# AHE.net
KiCad netlist of a schematic drawn in EAGLE
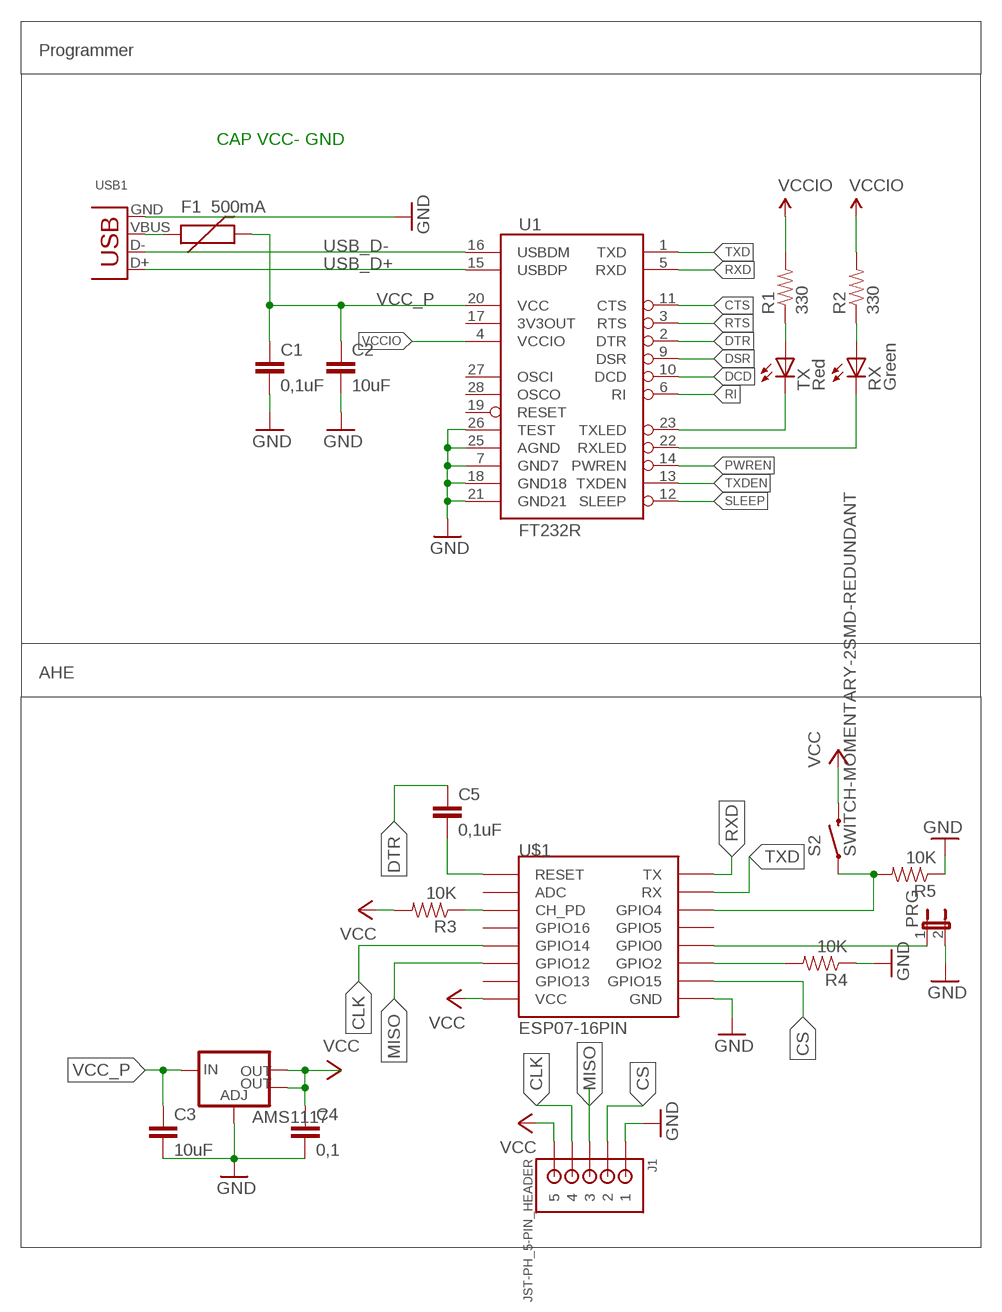
[diagram p0: schematic, sheet 1]

(export (version "E")
  (design (tool "Eeschema 10.0.6"))
  (components
    (comp (ref "AMS1117")
      (value "V_REG_LM1117SOT223")
      (footprint "eagle-import:SOT223")
      (libsource (lib "eagle-import") (part "V_REG_LM1117SOT223"))
    )
    (comp (ref "C1")
      (value "0,1uF")
      (footprint "eagle-import:0805-CAP")
      (libsource (lib "eagle-import") (part "10UF10V10%(0805)"))
    )
    (comp (ref "C2")
      (value "10uF")
      (footprint "eagle-import:0805-CAP")
      (libsource (lib "eagle-import") (part "10UF10V10%(0805)"))
    )
    (comp (ref "C3")
      (value "10uF")
      (footprint "eagle-import:0805-CAP")
      (libsource (lib "eagle-import") (part "10UF10V10%(0805)"))
    )
    (comp (ref "C4")
      (value "0,1")
      (footprint "eagle-import:0805-CAP")
      (libsource (lib "eagle-import") (part "10UF10V10%(0805)"))
    )
    (comp (ref "C5")
      (value "0,1uF")
      (footprint "eagle-import:0805-CAP")
      (libsource (lib "eagle-import") (part "10UF10V10%(0805)"))
    )
    (comp (ref "F1")
      (value "500mA")
      (footprint "eagle-import:PTC-1206")
      (libsource (lib "eagle-import") (part "PTCSMD"))
    )
    (comp (ref "J1")
      (value "JST-PH_5-PIN_HEADER")
      (footprint "eagle-import:JST_B5B-PH_HEADER")
      (libsource (lib "eagle-import") (part "JST-PH_5-PIN_HEADER"))
    )
    (comp (ref "PRG")
      (value "JP1E")
      (footprint "eagle-import:JP1")
      (libsource (lib "eagle-import") (part "JP1E"))
    )
    (comp (ref "R1")
      (value "330")
      (footprint "eagle-import:0805")
      (libsource (lib "eagle-import") (part "0.22OHM-1/4W-1%(0805)"))
    )
    (comp (ref "R2")
      (value "330")
      (footprint "eagle-import:0805")
      (libsource (lib "eagle-import") (part "0.22OHM-1/4W-1%(0805)"))
    )
    (comp (ref "R3")
      (value "10K")
      (footprint "eagle-import:0805")
      (libsource (lib "eagle-import") (part "0.22OHM-1/4W-1%(0805)"))
    )
    (comp (ref "R4")
      (value "10K")
      (footprint "eagle-import:0805")
      (libsource (lib "eagle-import") (part "0.22OHM-1/4W-1%(0805)"))
    )
    (comp (ref "R5")
      (value "10K")
      (footprint "eagle-import:0805")
      (libsource (lib "eagle-import") (part "0.22OHM-1/4W-1%(0805)"))
    )
    (comp (ref "RX")
      (value "Green")
      (footprint "eagle-import:SML0805")
      (libsource (lib "eagle-import") (part "LEDSML0805"))
    )
    (comp (ref "S2")
      (value "SWITCH-MOMENTARY-2SMD-REDUNDANT")
      (footprint "eagle-import:TACTILE-SWITCH-SMD")
      (libsource (lib "eagle-import") (part "SWITCH-MOMENTARY-2SMD-REDUNDANT"))
    )
    (comp (ref "TX")
      (value "Red")
      (footprint "eagle-import:SML0805")
      (libsource (lib "eagle-import") (part "LEDSML0805"))
    )
    (comp (ref "U$1")
      (value "ESP07-16PIN")
      (footprint "eagle-import:ESP07-16PIN")
      (libsource (lib "eagle-import") (part "ESP07-16PIN"))
    )
    (comp (ref "U1")
      (value "FT232R")
      (footprint "eagle-import:SSOP28DB")
      (libsource (lib "eagle-import") (part "FT232RLSSOP"))
    )
    (comp (ref "USB1")
      (value "USB-MB-S")
      (footprint "eagle-import:USB-MB-S")
      (libsource (lib "eagle-import") (part "USB-MB-S"))
    )
  )
  (nets
    (net (code "1") (name "/USB_D+") (class "Default")
      (node (ref "U1") (pin "15") (pinfunction "USBDP_15") (pintype "bidirectional"))
      (node (ref "USB1") (pin "D+") (pinfunction "D+_D+") (pintype "bidirectional"))
    )
    (net (code "2") (name "/USB_D-") (class "Default")
      (node (ref "U1") (pin "16") (pinfunction "USBDM_16") (pintype "bidirectional"))
      (node (ref "USB1") (pin "D-") (pinfunction "D-_D-") (pintype "bidirectional"))
    )
    (net (code "3") (name "CLK") (class "Default")
      (node (ref "J1") (pin "P4") (pinfunction "4_P4") (pintype "bidirectional"))
      (node (ref "U$1") (pin "GPIO14") (pinfunction "GPIO14_GPIO14") (pintype "bidirectional"))
    )
    (net (code "4") (name "CS") (class "Default")
      (node (ref "J1") (pin "P2") (pinfunction "2_P2") (pintype "bidirectional"))
      (node (ref "U$1") (pin "GPIO15") (pinfunction "GPIO15_GPIO15") (pintype "bidirectional"))
    )
    (net (code "5") (name "CTS") (class "Default")
      (node (ref "U1") (pin "11") (pinfunction "CTS_11") (pintype "input"))
    )
    (net (code "6") (name "DCD") (class "Default")
      (node (ref "U1") (pin "10") (pinfunction "DCD_10") (pintype "input"))
    )
    (net (code "7") (name "DSR") (class "Default")
      (node (ref "U1") (pin "9") (pinfunction "DSR_9") (pintype "input"))
    )
    (net (code "8") (name "DTR") (class "Default")
      (node (ref "C5") (pin "1") (pinfunction "1_1") (pintype "passive"))
      (node (ref "U1") (pin "2") (pinfunction "DTR_2") (pintype "output"))
    )
    (net (code "9") (name "GND") (class "Default")
      (node (ref "AMS1117") (pin "1") (pinfunction "ADJ_1") (pintype "input"))
      (node (ref "C1") (pin "2") (pinfunction "2_2") (pintype "passive"))
      (node (ref "C2") (pin "2") (pinfunction "2_2") (pintype "passive"))
      (node (ref "C3") (pin "2") (pinfunction "2_2") (pintype "passive"))
      (node (ref "C4") (pin "2") (pinfunction "2_2") (pintype "passive"))
      (node (ref "J1") (pin "P1") (pinfunction "1_P1") (pintype "bidirectional"))
      (node (ref "PRG") (pin "2") (pinfunction "2_2") (pintype "passive"))
      (node (ref "R4") (pin "1") (pinfunction "1_1") (pintype "passive"))
      (node (ref "R5") (pin "1") (pinfunction "1_1") (pintype "passive"))
      (node (ref "U$1") (pin "GND") (pinfunction "GND_GND") (pintype "bidirectional"))
      (node (ref "U1") (pin "18") (pinfunction "GND18_18") (pintype "power_in"))
      (node (ref "U1") (pin "21") (pinfunction "GND21_21") (pintype "power_in"))
      (node (ref "U1") (pin "25") (pinfunction "AGND_25") (pintype "power_in"))
      (node (ref "U1") (pin "26") (pinfunction "TEST_26") (pintype "input"))
      (node (ref "U1") (pin "7") (pinfunction "GND7_7") (pintype "power_in"))
      (node (ref "USB1") (pin "GND") (pinfunction "GND_GND") (pintype "bidirectional"))
    )
    (net (code "10") (name "MISO") (class "Default")
      (node (ref "J1") (pin "P3") (pinfunction "3_P3") (pintype "bidirectional"))
      (node (ref "U$1") (pin "GPIO12") (pinfunction "GPIO12_GPIO12") (pintype "bidirectional"))
    )
    (net (code "11") (name "Net-(F1-Pad1)") (class "Default")
      (node (ref "F1") (pin "1") (pinfunction "1_1") (pintype "bidirectional"))
      (node (ref "USB1") (pin "VBUS") (pinfunction "VBUS_VBUS") (pintype "bidirectional"))
    )
    (net (code "12") (name "Net-(PRG-Pad1)") (class "Default")
      (node (ref "PRG") (pin "1") (pinfunction "1_1") (pintype "passive"))
      (node (ref "U$1") (pin "GPIO0") (pinfunction "GPIO0_GPIO0") (pintype "bidirectional"))
    )
    (net (code "13") (name "Net-(R1-Pad1)") (class "Default")
      (node (ref "R1") (pin "1") (pinfunction "1_1") (pintype "passive"))
      (node (ref "TX") (pin "A") (pinfunction "A_A") (pintype "passive"))
    )
    (net (code "14") (name "Net-(R2-Pad1)") (class "Default")
      (node (ref "R2") (pin "1") (pinfunction "1_1") (pintype "passive"))
      (node (ref "RX") (pin "A") (pinfunction "A_A") (pintype "passive"))
    )
    (net (code "15") (name "Net-(R3-Pad1)") (class "Default")
      (node (ref "R3") (pin "1") (pinfunction "1_1") (pintype "passive"))
      (node (ref "U$1") (pin "CH_PD") (pinfunction "CH_PD_CH_PD") (pintype "bidirectional"))
    )
    (net (code "16") (name "Net-(R4-Pad2)") (class "Default")
      (node (ref "R4") (pin "2") (pinfunction "2_2") (pintype "passive"))
      (node (ref "U$1") (pin "GPIO2") (pinfunction "GPIO2_GPIO2") (pintype "bidirectional"))
    )
    (net (code "17") (name "Net-(R5-Pad2)") (class "Default")
      (node (ref "R5") (pin "2") (pinfunction "2_2") (pintype "passive"))
      (node (ref "S2") (pin "1") (pinfunction "1_1") (pintype "passive"))
      (node (ref "S2") (pin "2") (pinfunction "1_2") (pintype "passive"))
      (node (ref "U$1") (pin "GPIO4") (pinfunction "GPIO4_GPIO4") (pintype "bidirectional"))
    )
    (net (code "18") (name "Net-(U$1-RESET)") (class "Default")
      (node (ref "C5") (pin "2") (pinfunction "2_2") (pintype "passive"))
      (node (ref "U$1") (pin "REST") (pinfunction "RESET_REST") (pintype "bidirectional"))
    )
    (net (code "19") (name "Net-(U1-RXLED)") (class "Default")
      (node (ref "RX") (pin "C") (pinfunction "C_C") (pintype "passive"))
      (node (ref "U1") (pin "22") (pinfunction "RXLED_22") (pintype "input"))
    )
    (net (code "20") (name "Net-(U1-TXLED)") (class "Default")
      (node (ref "TX") (pin "C") (pinfunction "C_C") (pintype "passive"))
      (node (ref "U1") (pin "23") (pinfunction "TXLED_23") (pintype "input"))
    )
    (net (code "21") (name "PWREN") (class "Default")
      (node (ref "U1") (pin "14") (pinfunction "PWREN_14") (pintype "input"))
    )
    (net (code "22") (name "RI") (class "Default")
      (node (ref "U1") (pin "6") (pinfunction "RI_6") (pintype "input"))
    )
    (net (code "23") (name "RTS") (class "Default")
      (node (ref "U1") (pin "3") (pinfunction "RTS_3") (pintype "output"))
    )
    (net (code "24") (name "RXD") (class "Default")
      (node (ref "U$1") (pin "TX") (pinfunction "TX_TX") (pintype "bidirectional"))
      (node (ref "U1") (pin "5") (pinfunction "RXD_5") (pintype "input"))
    )
    (net (code "25") (name "SLEEP") (class "Default")
      (node (ref "U1") (pin "12") (pinfunction "SLEEP_12") (pintype "input"))
    )
    (net (code "26") (name "TXD") (class "Default")
      (node (ref "U$1") (pin "RX") (pinfunction "RX_RX") (pintype "bidirectional"))
      (node (ref "U1") (pin "1") (pinfunction "TXD_1") (pintype "output"))
    )
    (net (code "27") (name "TXDEN") (class "Default")
      (node (ref "U1") (pin "13") (pinfunction "TXDEN_13") (pintype "input"))
    )
    (net (code "28") (name "VCC") (class "Default")
      (node (ref "AMS1117") (pin "2") (pinfunction "OUT_2") (pintype "output"))
      (node (ref "AMS1117") (pin "4") (pinfunction "OUT_4") (pintype "output"))
      (node (ref "C4") (pin "1") (pinfunction "1_1") (pintype "passive"))
      (node (ref "J1") (pin "P5") (pinfunction "5_P5") (pintype "bidirectional"))
      (node (ref "R3") (pin "2") (pinfunction "2_2") (pintype "passive"))
      (node (ref "S2") (pin "3") (pinfunction "2_3") (pintype "passive"))
      (node (ref "S2") (pin "4") (pinfunction "2_4") (pintype "passive"))
      (node (ref "U$1") (pin "VCC") (pinfunction "VCC_VCC") (pintype "bidirectional"))
    )
    (net (code "29") (name "VCCIO") (class "Default")
      (node (ref "R1") (pin "2") (pinfunction "2_2") (pintype "passive"))
      (node (ref "R2") (pin "2") (pinfunction "2_2") (pintype "passive"))
      (node (ref "U1") (pin "4") (pinfunction "VCCIO_4") (pintype "power_in"))
    )
    (net (code "30") (name "VCC_P") (class "Default")
      (node (ref "AMS1117") (pin "3") (pinfunction "IN_3") (pintype "input"))
      (node (ref "C1") (pin "1") (pinfunction "1_1") (pintype "passive"))
      (node (ref "C2") (pin "1") (pinfunction "1_1") (pintype "passive"))
      (node (ref "C3") (pin "1") (pinfunction "1_1") (pintype "passive"))
      (node (ref "F1") (pin "2") (pinfunction "2_2") (pintype "bidirectional"))
      (node (ref "U1") (pin "20") (pinfunction "VCC_20") (pintype "power_in"))
    )
    (net (code "31") (name "unconnected-(U$1-PadADC)") (class "Default")
      (node (ref "U$1") (pin "ADC") (pinfunction "ADC_ADC") (pintype "bidirectional"))
    )
    (net (code "32") (name "unconnected-(U$1-PadGPIO5)") (class "Default")
      (node (ref "U$1") (pin "GPIO5") (pinfunction "GPIO5_GPIO5") (pintype "bidirectional"))
    )
    (net (code "33") (name "unconnected-(U$1-PadGPIO13)") (class "Default")
      (node (ref "U$1") (pin "GPIO13") (pinfunction "GPIO13_GPIO13") (pintype "bidirectional"))
    )
    (net (code "34") (name "unconnected-(U$1-PadGPIO16)") (class "Default")
      (node (ref "U$1") (pin "GPIO16") (pinfunction "GPIO16_GPIO16") (pintype "bidirectional"))
    )
    (net (code "35") (name "unconnected-(U1-3V3OUT-Pad17)") (class "Default")
      (node (ref "U1") (pin "17") (pinfunction "3V3OUT_17") (pintype "output"))
    )
    (net (code "36") (name "unconnected-(U1-OSCI-Pad27)") (class "Default")
      (node (ref "U1") (pin "27") (pinfunction "OSCI_27") (pintype "input"))
    )
    (net (code "37") (name "unconnected-(U1-OSCO-Pad28)") (class "Default")
      (node (ref "U1") (pin "28") (pinfunction "OSCO_28") (pintype "output"))
    )
    (net (code "38") (name "unconnected-(U1-RESET-Pad19)") (class "Default")
      (node (ref "U1") (pin "19") (pinfunction "RESET_19") (pintype "input"))
    )
  )
)
